# CANbus.net
KiCad netlist of a schematic drawn in Altium Designer
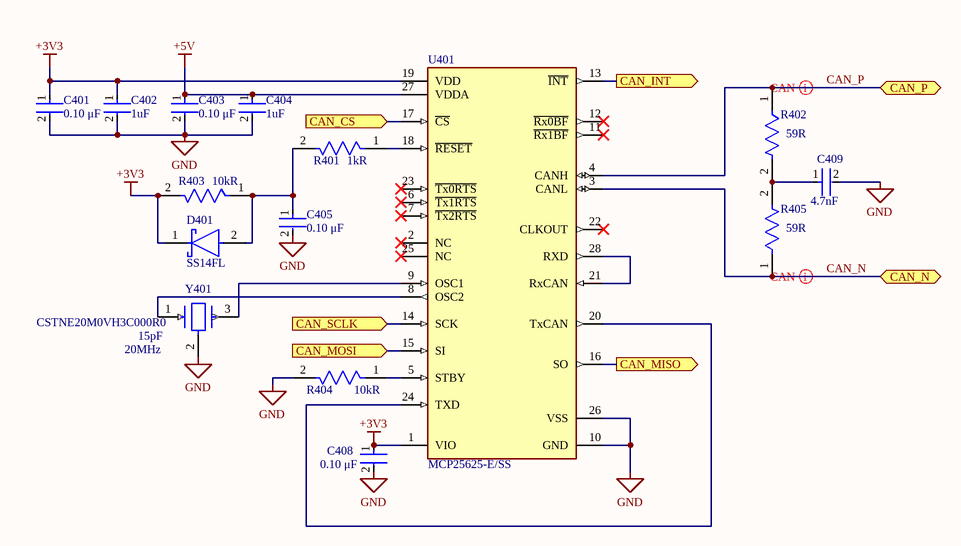
[diagram p0: CANbus.SchDoc]

(export (version "E")
  (design (tool "Eeschema 10.0.6"))
  (components
    (comp (ref "C401")
      (value "C0603C104K5RACAUTO")
      (footprint "FP-C0603C-CF-MFG")
      (description "CAP CER 0.1UF 50V X7R 0603")
      (fields
        (field (name "MANUFACTURER") "KEMET")
        (field (name "OCTOPART") "https://octopart.com/c0603c104k5racauto-kemet-12563741")
        (field (name "CAPACITANCE") "0.10 μF")
      )
      (libsource (lib "Altium Content Vault") (part "b4654b650e69147ec39a6b967a45e02"))
    )
    (comp (ref "C402")
      (value "C0603C105K4RACAUTO")
      (footprint "FP-C0603C-CJ-MFG")
      (description "CAP CER 0603 1UF 16V X7R 10%")
      (fields
        (field (name "MANUFACTURER") "KEMET")
        (field (name "OCTOPART") "https://octopart.com/c0603c105k4racauto-kemet-91328491")
        (field (name "CAPACITANCE") "1uF")
      )
      (libsource (lib "Altium Content Vault") (part "b4654b650e69147ec39a6b967a45e02"))
    )
    (comp (ref "C403")
      (value "C0603C104K5RACAUTO")
      (footprint "FP-C0603C-CF-MFG")
      (description "CAP CER 0.1UF 50V X7R 0603")
      (fields
        (field (name "MANUFACTURER") "KEMET")
        (field (name "OCTOPART") "https://octopart.com/c0603c104k5racauto-kemet-12563741")
        (field (name "CAPACITANCE") "0.10 μF")
      )
      (libsource (lib "Altium Content Vault") (part "b4654b650e69147ec39a6b967a45e02"))
    )
    (comp (ref "C404")
      (value "C0603C105K4RACAUTO")
      (footprint "FP-C0603C-CJ-MFG")
      (description "CAP CER 0603 1UF 16V X7R 10%")
      (fields
        (field (name "MANUFACTURER") "KEMET")
        (field (name "OCTOPART") "https://octopart.com/c0603c105k4racauto-kemet-91328491")
        (field (name "CAPACITANCE") "1uF")
      )
      (libsource (lib "Altium Content Vault") (part "b4654b650e69147ec39a6b967a45e02"))
    )
    (comp (ref "C405")
      (value "C0603C104K5RACAUTO")
      (footprint "FP-C0603C-CF-MFG")
      (description "CAP CER 0.1UF 50V X7R 0603")
      (fields
        (field (name "MANUFACTURER") "KEMET")
        (field (name "OCTOPART") "https://octopart.com/c0603c104k5racauto-kemet-12563741")
        (field (name "CAPACITANCE") "0.10 μF")
      )
      (libsource (lib "Altium Content Vault") (part "b4654b650e69147ec39a6b967a45e02"))
    )
    (comp (ref "C408")
      (value "C0603C104K5RACAUTO")
      (footprint "FP-C0603C-CF-MFG")
      (description "CAP CER 0.1UF 50V X7R 0603")
      (fields
        (field (name "MANUFACTURER") "KEMET")
        (field (name "OCTOPART") "https://octopart.com/c0603c104k5racauto-kemet-12563741")
        (field (name "CAPACITANCE") "0.10 μF")
      )
      (libsource (lib "Altium Content Vault") (part "b4654b650e69147ec39a6b967a45e02"))
    )
    (comp (ref "C409")
      (value "GRM155R72A472KA01D")
      (footprint "FP-GRM155-0_05-MFG")
      (description "Chip Multilayer Ceramic Capacitors for General Purpose, 0402, 4700pF, X7R, 15%, 10%, 100V")
      (fields
        (field (name "VOLTAGE") "100V")
        (field (name "CAPACITANCE") "4.7nF")
        (field (name "TOLERANCE") "10%")
      )
      (libsource (lib "Altium Content Vault") (part "02cd4be3c70576c341d710602a673aa"))
    )
    (comp (ref "D401")
      (value "SS14FL")
      (footprint "FP-425AD-MFG")
      (description "DIODE SCHOTTKY 40V 1A SOD123F")
      (fields
        (field (name "MANUFACTURER") "ON Semiconductor")
        (field (name "OCTOPART") "https://octopart.com/ss14fl-on+semiconductor-84331601")
      )
      (libsource (lib "Altium Content Vault") (part "c1678fac7984e62e0809fbf79c06691"))
    )
    (comp (ref "R401")
      (value "RMCF0603JT1K00")
      (footprint "FP-RMCF0603-IPC_C")
      (description "1kΩ ±5% 0.1W 0603 Thick Film Chip Resistor AEC-Q200 compliant")
      (fields (field (name "RESISTANCE") "1kR") (field (name "TOLERANCE") "5%"))
      (libsource (lib "Altium Content Vault") (part "1029c3af85768c4190bb7ad29bc67b5"))
    )
    (comp (ref "R402")
      (value "CRCW060359R0FKEAHP")
      (footprint "FP-CRCW0603-HPe3-IPC_A")
      (description "RES Thick Film, 59Ω, 1%, 0.33W, 100ppm/°C, 0603")
      (fields (field (name "RESISTANCE") "59R") (field (name "TOLERANCE") "1%"))
      (libsource (lib "Altium Content Vault") (part "1029c3af85768c4190bb7ad29bc67b5"))
    )
    (comp (ref "R403")
      (value "RMCF0603JT10K0")
      (footprint "FP-RMCF0603-IPC_C")
      (description "10kΩ ±5% 0.1W 0603 Thick Film Chip Resistor AEC-Q200 compliant")
      (fields (field (name "TOLERANCE") "5%") (field (name "RESISTANCE") "10kR"))
      (libsource (lib "Altium Content Vault") (part "1029c3af85768c4190bb7ad29bc67b5"))
    )
    (comp (ref "R404")
      (value "RMCF0603JT10K0")
      (footprint "FP-RMCF0603-IPC_C")
      (description "10kΩ ±5% 0.1W 0603 Thick Film Chip Resistor AEC-Q200 compliant")
      (fields (field (name "TOLERANCE") "5%") (field (name "RESISTANCE") "10kR"))
      (libsource (lib "Altium Content Vault") (part "1029c3af85768c4190bb7ad29bc67b5"))
    )
    (comp (ref "R405")
      (value "CRCW060359R0FKEAHP")
      (footprint "FP-CRCW0603-HPe3-IPC_A")
      (description "RES Thick Film, 59Ω, 1%, 0.33W, 100ppm/°C, 0603")
      (fields (field (name "RESISTANCE") "59R") (field (name "TOLERANCE") "1%"))
      (libsource (lib "Altium Content Vault") (part "1029c3af85768c4190bb7ad29bc67b5"))
    )
    (comp (ref "U401")
      (value "MCP25625-E/SS")
      (footprint "FP-C04-073-MFG")
      (description "IC TXRX CAN CTLR EXT TEMP 28SSOP")
      (fields
        (field (name "OCTOPART") "https://octopart.com/mcp25625-e%2Fss-microchip-38886007")
        (field (name "MANUFACTURER") "Microchip")
      )
      (libsource (lib "Altium Content Vault") (part "0a2f9e3bbb471d56250278b44f96a4f"))
    )
    (comp (ref "Y401")
      (value "CSTNE20M0VH3C000R0")
      (footprint "FP-CSTNE20M0VH3C000R0-MFG")
      (description "CERAMIC RES 20.0000MHZ 15PF SMD")
      (fields (field (name "FREQUENCY") "20MHz") (field (name "CAPACITANCE") "15pF"))
      (libsource (lib "Altium Content Vault") (part "7d37667f5012bb31280c8009ddd0b1c"))
    )
  )
  (nets
    (net (code "1") (name "+3V3") (class "Default")
      (node (ref "C401") (pin "1") (pinfunction "1_1") (pintype "passive"))
      (node (ref "C402") (pin "1") (pinfunction "1_1") (pintype "passive"))
      (node (ref "C408") (pin "1") (pinfunction "1_1") (pintype "passive"))
      (node (ref "D401") (pin "1") (pinfunction "C_1") (pintype "passive"))
      (node (ref "R403") (pin "2") (pinfunction "2_2") (pintype "passive"))
      (node (ref "U401") (pin "1") (pinfunction "VIO_1") (pintype "power_in"))
      (node (ref "U401") (pin "19") (pinfunction "VDD_19") (pintype "power_in"))
    )
    (net (code "2") (name "+5V") (class "Default")
      (node (ref "C403") (pin "1") (pinfunction "1_1") (pintype "passive"))
      (node (ref "C404") (pin "1") (pinfunction "1_1") (pintype "passive"))
      (node (ref "U401") (pin "27") (pinfunction "VDDA_27") (pintype "power_in"))
    )
    (net (code "3") (name "/CAN_CS") (class "Default")
      (node (ref "U401") (pin "17") (pinfunction "~{CS}_17") (pintype "input"))
    )
    (net (code "4") (name "/CAN_INT") (class "Default")
      (node (ref "U401") (pin "13") (pinfunction "~{INT}_13") (pintype "output"))
    )
    (net (code "5") (name "/CAN_MISO") (class "Default")
      (node (ref "U401") (pin "16") (pinfunction "SO_16") (pintype "output"))
    )
    (net (code "6") (name "/CAN_MOSI") (class "Default")
      (node (ref "U401") (pin "15") (pinfunction "SI_15") (pintype "input"))
    )
    (net (code "7") (name "/CAN_N") (class "Default")
      (node (ref "R405") (pin "1") (pinfunction "1_1") (pintype "passive"))
      (node (ref "U401") (pin "3") (pinfunction "CANL_3") (pintype "bidirectional"))
    )
    (net (code "8") (name "/CAN_P") (class "Default")
      (node (ref "R402") (pin "1") (pinfunction "1_1") (pintype "passive"))
      (node (ref "U401") (pin "4") (pinfunction "CANH_4") (pintype "bidirectional"))
    )
    (net (code "9") (name "/CAN_SCLK") (class "Default")
      (node (ref "U401") (pin "14") (pinfunction "SCK_14") (pintype "input"))
    )
    (net (code "10") (name "GND") (class "Default")
      (node (ref "C401") (pin "2") (pinfunction "2_2") (pintype "passive"))
      (node (ref "C402") (pin "2") (pinfunction "2_2") (pintype "passive"))
      (node (ref "C403") (pin "2") (pinfunction "2_2") (pintype "passive"))
      (node (ref "C404") (pin "2") (pinfunction "2_2") (pintype "passive"))
      (node (ref "C405") (pin "2") (pinfunction "2_2") (pintype "passive"))
      (node (ref "C408") (pin "2") (pinfunction "2_2") (pintype "passive"))
      (node (ref "C409") (pin "2") (pinfunction "2_2") (pintype "passive"))
      (node (ref "R404") (pin "2") (pinfunction "2_2") (pintype "passive"))
      (node (ref "U401") (pin "10") (pinfunction "GND_10") (pintype "power_in"))
      (node (ref "U401") (pin "26") (pinfunction "VSS_26") (pintype "power_in"))
      (node (ref "Y401") (pin "2") (pinfunction "GND_2") (pintype "power_in"))
    )
    (net (code "11") (name "Net-(C409-Pad1)") (class "Default")
      (node (ref "C409") (pin "1") (pinfunction "1_1") (pintype "passive"))
      (node (ref "R402") (pin "2") (pinfunction "2_2") (pintype "passive"))
      (node (ref "R405") (pin "2") (pinfunction "2_2") (pintype "passive"))
    )
    (net (code "12") (name "Net-(D401-A)") (class "Default")
      (node (ref "C405") (pin "1") (pinfunction "1_1") (pintype "passive"))
      (node (ref "D401") (pin "2") (pinfunction "A_2") (pintype "passive"))
      (node (ref "R401") (pin "2") (pinfunction "2_2") (pintype "passive"))
      (node (ref "R403") (pin "1") (pinfunction "1_1") (pintype "passive"))
    )
    (net (code "13") (name "Net-(U401-OSC1)") (class "Default")
      (node (ref "U401") (pin "9") (pinfunction "OSC1_9") (pintype "input"))
      (node (ref "Y401") (pin "3") (pinfunction "Output_3") (pintype "output"))
    )
    (net (code "14") (name "Net-(U401-OSC2)") (class "Default")
      (node (ref "U401") (pin "8") (pinfunction "OSC2_8") (pintype "output"))
      (node (ref "Y401") (pin "1") (pinfunction "Input_1") (pintype "input"))
    )
    (net (code "15") (name "Net-(U401-RXD)") (class "Default")
      (node (ref "U401") (pin "21") (pinfunction "RxCAN_21") (pintype "input"))
      (node (ref "U401") (pin "28") (pinfunction "RXD_28") (pintype "output"))
    )
    (net (code "16") (name "Net-(U401-STBY)") (class "Default")
      (node (ref "R404") (pin "1") (pinfunction "1_1") (pintype "passive"))
      (node (ref "U401") (pin "5") (pinfunction "STBY_5") (pintype "input"))
    )
    (net (code "17") (name "Net-(U401-TXD)") (class "Default")
      (node (ref "U401") (pin "20") (pinfunction "TxCAN_20") (pintype "output"))
      (node (ref "U401") (pin "24") (pinfunction "TXD_24") (pintype "input"))
    )
    (net (code "18") (name "Net-(U401-~{RESET})") (class "Default")
      (node (ref "R401") (pin "1") (pinfunction "1_1") (pintype "passive"))
      (node (ref "U401") (pin "18") (pinfunction "~{RESET}_18") (pintype "input"))
    )
    (net (code "19") (name "unconnected-(U401-CLKOUT-Pad22)") (class "Default")
      (node (ref "U401") (pin "22") (pinfunction "CLKOUT_22") (pintype "output+no_connect"))
    )
    (net (code "20") (name "unconnected-(U401-NC-Pad2)") (class "Default")
      (node (ref "U401") (pin "2") (pinfunction "NC_2") (pintype "passive+no_connect"))
    )
    (net (code "21") (name "unconnected-(U401-NC-Pad25)") (class "Default")
      (node (ref "U401") (pin "25") (pinfunction "NC_25") (pintype "passive+no_connect"))
    )
    (net (code "22") (name "unconnected-(U401-~{Rx0BF}-Pad12)") (class "Default")
      (node (ref "U401") (pin "12") (pinfunction "~{Rx0BF}_12") (pintype "output+no_connect"))
    )
    (net (code "23") (name "unconnected-(U401-~{Rx1BF}-Pad11)") (class "Default")
      (node (ref "U401") (pin "11") (pinfunction "~{Rx1BF}_11") (pintype "output+no_connect"))
    )
    (net (code "24") (name "unconnected-(U401-~{Tx0RTS}-Pad23)") (class "Default")
      (node (ref "U401") (pin "23") (pinfunction "~{Tx0RTS}_23") (pintype "input+no_connect"))
    )
    (net (code "25") (name "unconnected-(U401-~{Tx1RTS}-Pad6)") (class "Default")
      (node (ref "U401") (pin "6") (pinfunction "~{Tx1RTS}_6") (pintype "input+no_connect"))
    )
    (net (code "26") (name "unconnected-(U401-~{Tx2RTS}-Pad7)") (class "Default")
      (node (ref "U401") (pin "7") (pinfunction "~{Tx2RTS}_7") (pintype "input+no_connect"))
    )
  )
)
